# solenoid.net
KiCad netlist of a schematic drawn in EAGLE
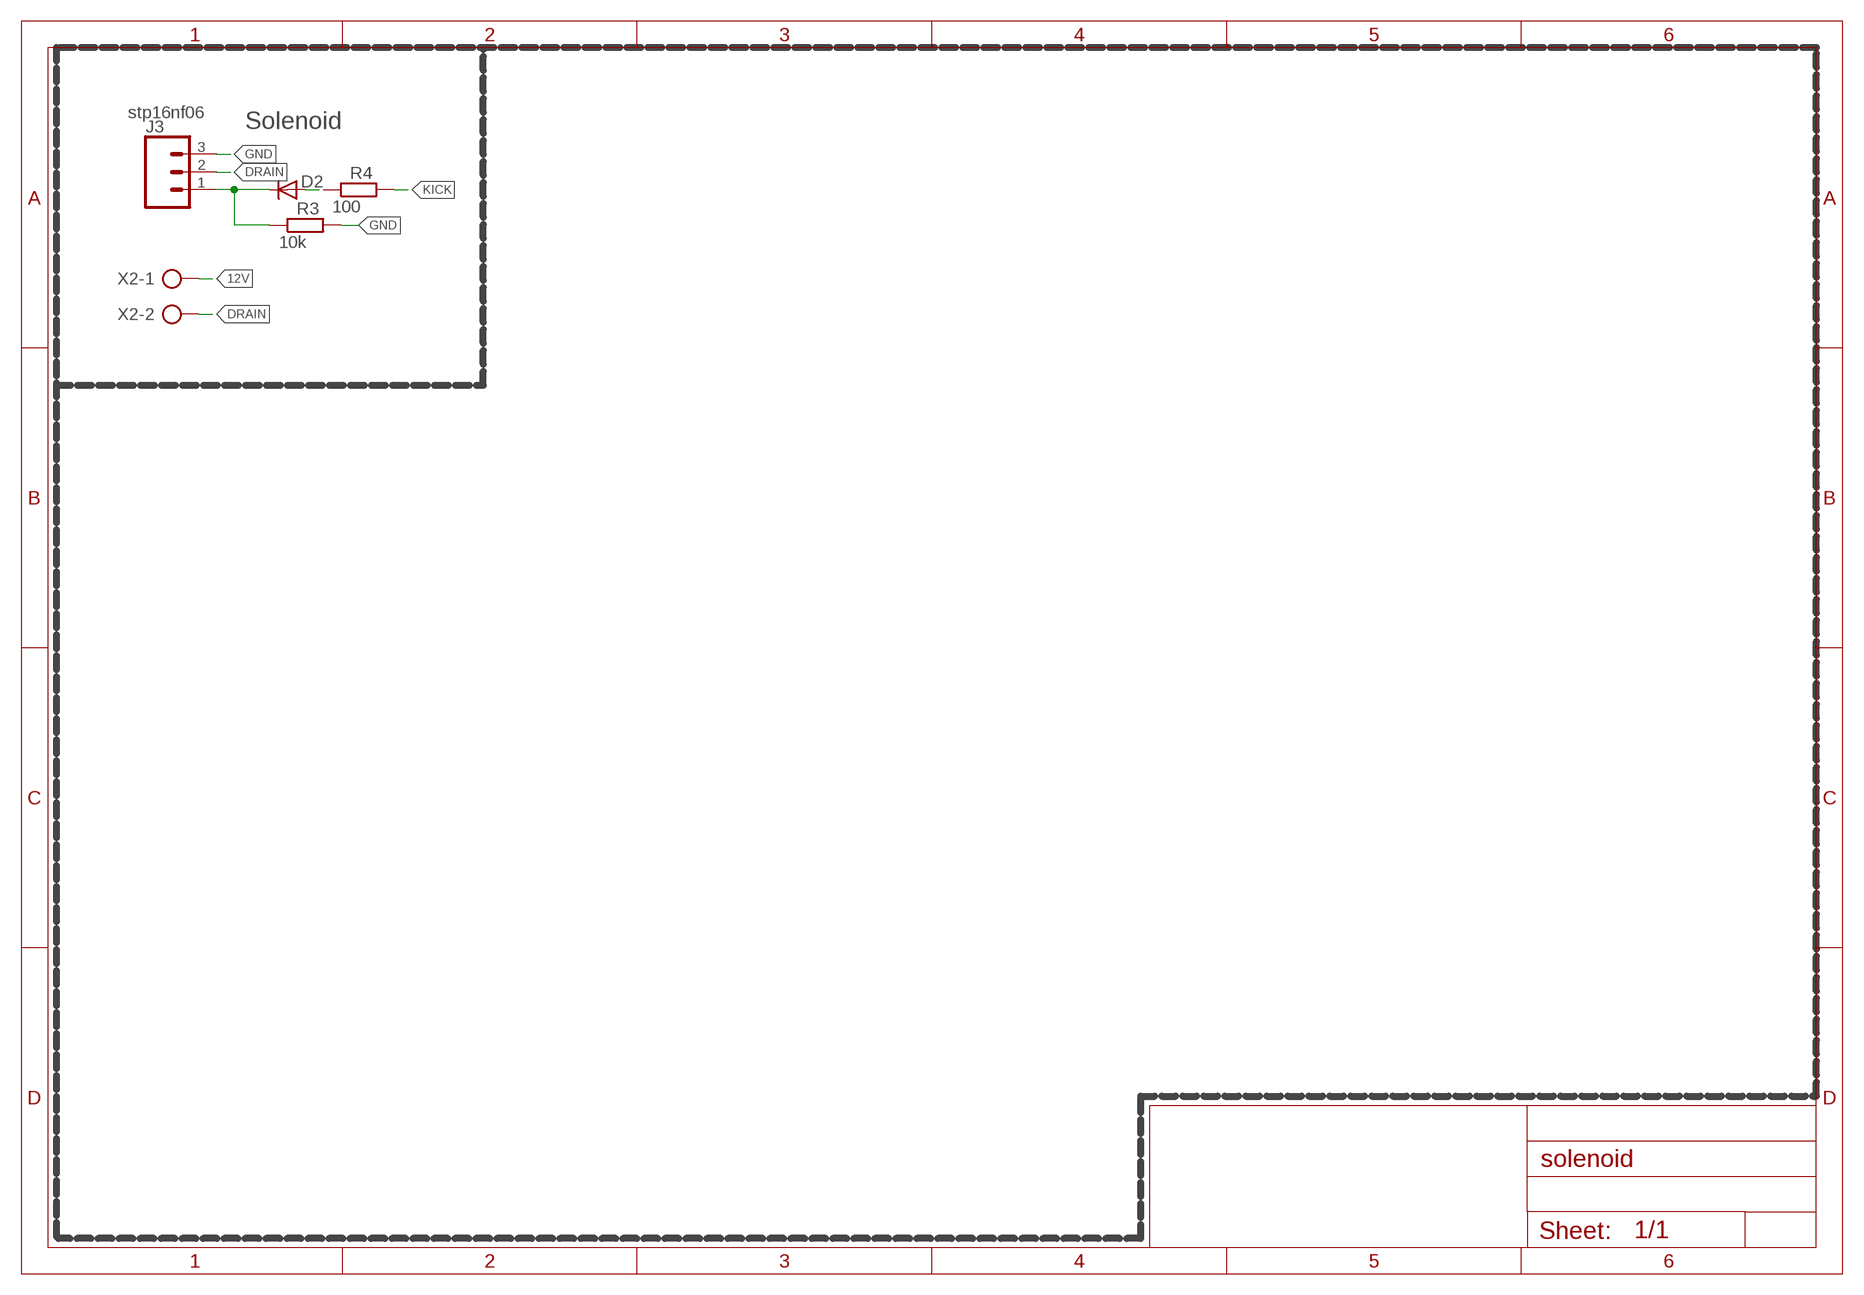
[diagram p0: schematic, sheet 1]

(export (version "E")
  (design (tool "Eeschema 10.0.6"))
  (components
    (comp (ref "D2")
      (value "1N4148")
      (footprint "eagle-import:DO35-7")
      (libsource (lib "eagle-import") (part "1N4148DO35-7"))
    )
    (comp (ref "J3")
      (value "455-1750-1-ND")
      (footprint "eagle-import:1X03")
      (libsource (lib "eagle-import") (part "CONN_03"))
    )
    (comp (ref "R3")
      (value "10k")
      (footprint "eagle-import:R1206")
      (libsource (lib "eagle-import") (part "RR1206"))
    )
    (comp (ref "R4")
      (value "100")
      (footprint "eagle-import:R1206")
      (libsource (lib "eagle-import") (part "RR1206"))
    )
    (comp (ref "X2")
      (value "AK500/2-H")
      (footprint "eagle-import:AK500_2-H")
      (libsource (lib "eagle-import") (part "AK500/2-H"))
    )
  )
  (nets
    (net (code "1") (name "12V") (class "Default")
      (node (ref "X2") (pin "1") (pinfunction "KL_1") (pintype "passive"))
    )
    (net (code "2") (name "DRAIN") (class "Default")
      (node (ref "J3") (pin "2") (pinfunction "2_2") (pintype "passive"))
      (node (ref "X2") (pin "2") (pinfunction "KL_2") (pintype "passive"))
    )
    (net (code "3") (name "GND") (class "Default")
      (node (ref "J3") (pin "3") (pinfunction "3_3") (pintype "passive"))
      (node (ref "R3") (pin "2") (pinfunction "2_2") (pintype "passive"))
    )
    (net (code "4") (name "KICK") (class "Default")
      (node (ref "R4") (pin "2") (pinfunction "2_2") (pintype "passive"))
    )
    (net (code "5") (name "Net-(D2-PadA)") (class "Default")
      (node (ref "D2") (pin "A") (pinfunction "A_A") (pintype "passive"))
      (node (ref "R4") (pin "1") (pinfunction "1_1") (pintype "passive"))
    )
    (net (code "6") (name "Net-(D2-PadC)") (class "Default")
      (node (ref "D2") (pin "C") (pinfunction "C_C") (pintype "passive"))
      (node (ref "J3") (pin "1") (pinfunction "1_1") (pintype "passive"))
      (node (ref "R3") (pin "1") (pinfunction "1_1") (pintype "passive"))
    )
  )
)
